# display.net
KiCad netlist of a schematic drawn in EAGLE
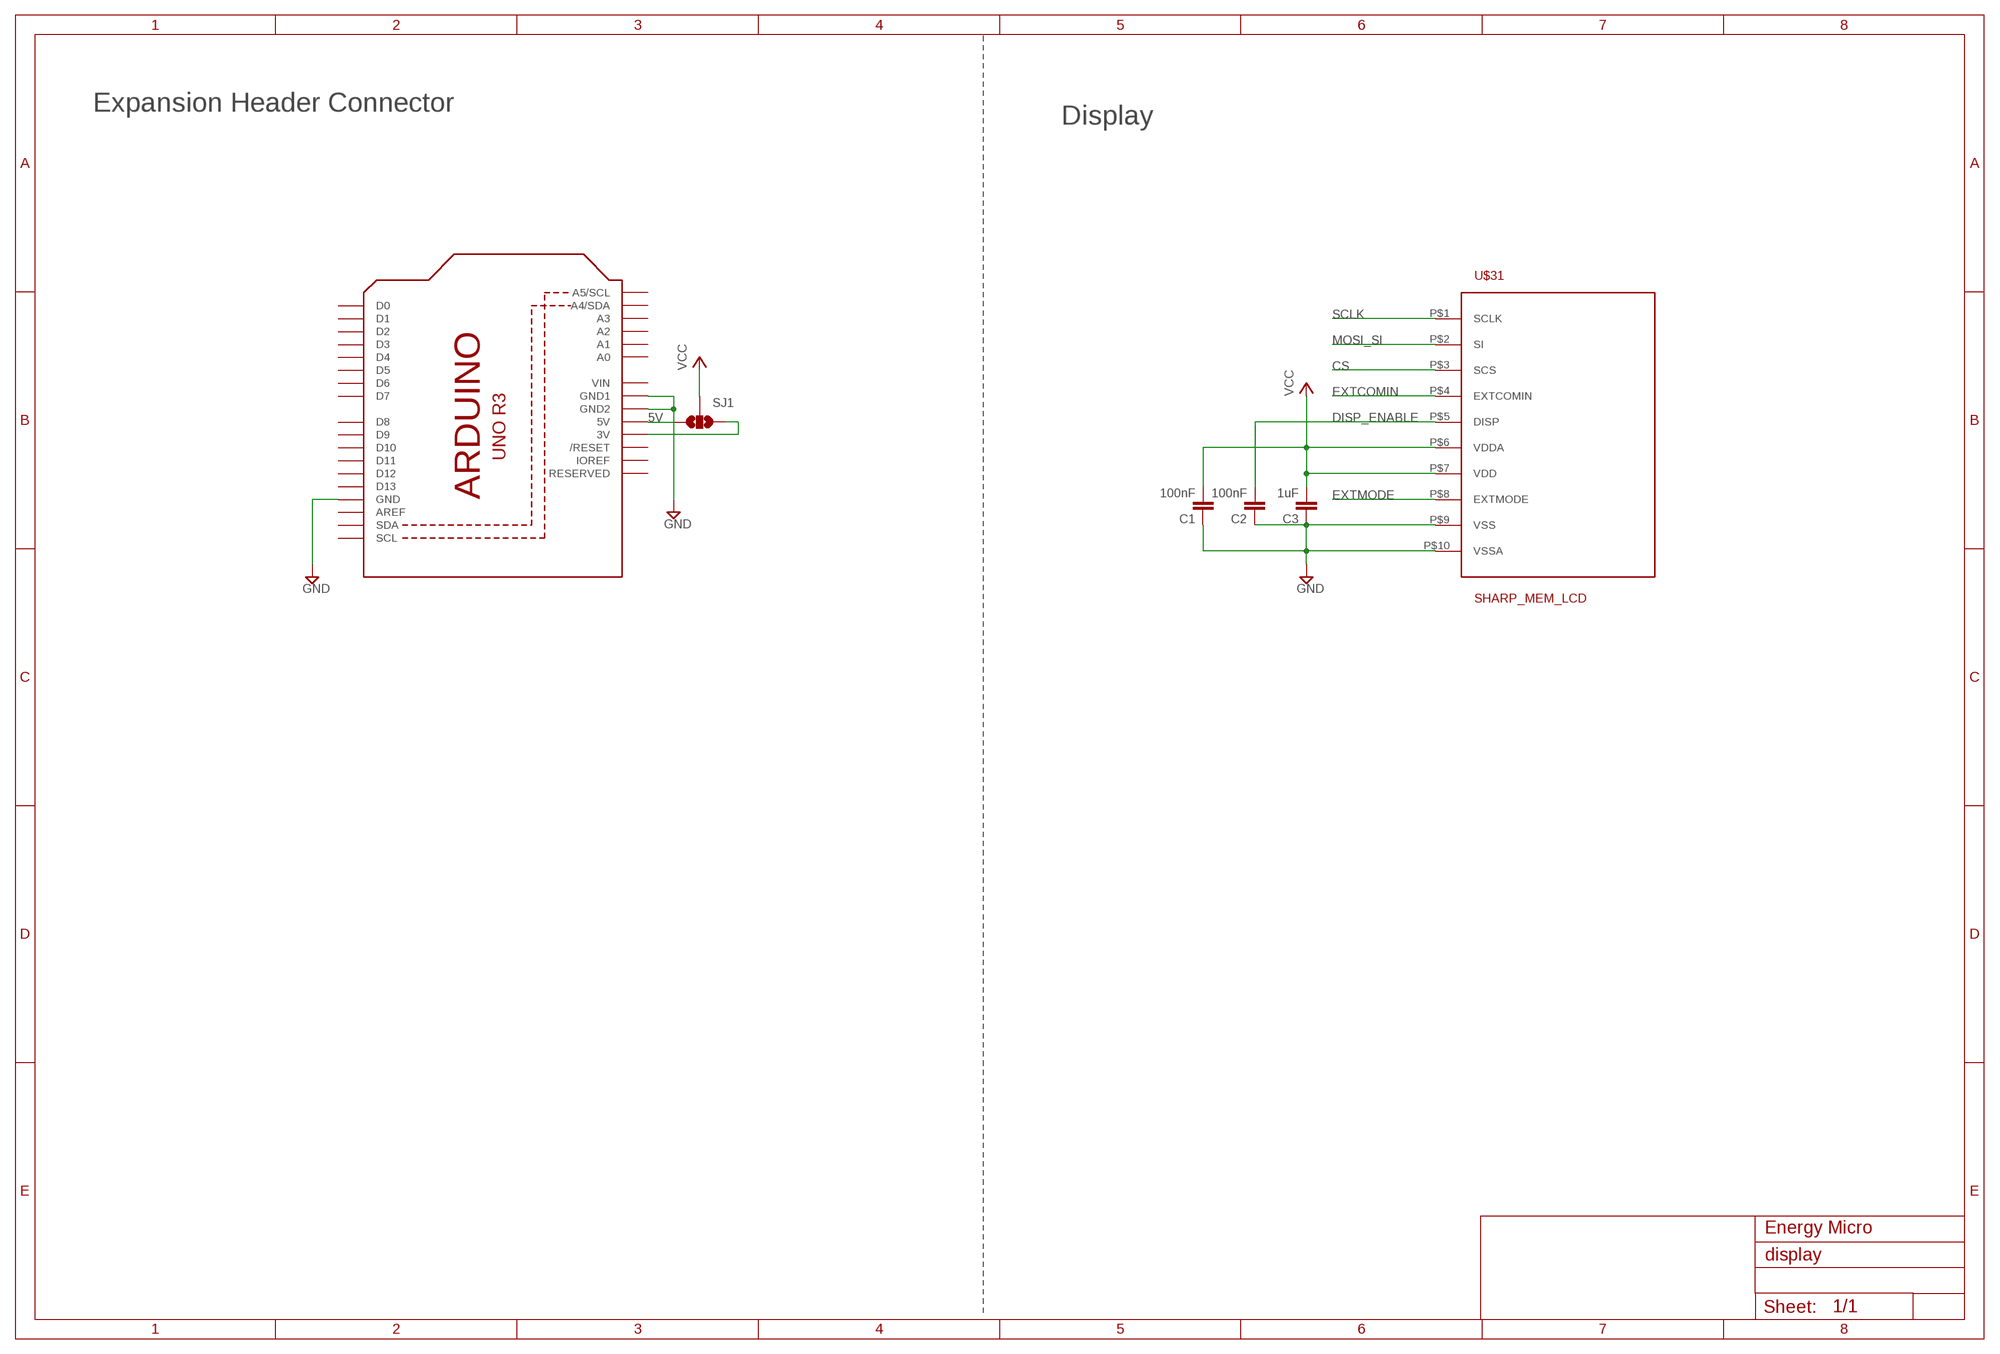
[diagram p0: schematic, sheet 1]

(export (version "E")
  (design (tool "Eeschema 10.0.6"))
  (components
    (comp (ref "C1")
      (value "100nF")
      (footprint "eagle-import:C0402K")
      (libsource (lib "eagle-import") (part "C-EUC0402K"))
    )
    (comp (ref "C2")
      (value "100nF")
      (footprint "eagle-import:C0402K")
      (libsource (lib "eagle-import") (part "C-EUC0402K"))
    )
    (comp (ref "C3")
      (value "1uF")
      (footprint "eagle-import:C0402K")
      (libsource (lib "eagle-import") (part "C-EUC0402K"))
    )
    (comp (ref "SJ1")
      (value "SOLDERJUMPER_2WAYT")
      (footprint "eagle-import:SJ_2")
      (libsource (lib "eagle-import") (part "SOLDERJUMPER_2WAYT"))
    )
    (comp (ref "U$31")
      (value "SHARP_MEM_LCD")
      (footprint "eagle-import:SHARP_MEM_LCD")
      (libsource (lib "eagle-import") (part "SHARP_MEM_LCD"))
    )
    (comp (ref "U1")
      (value "ARDUINOR3-MINI")
      (footprint "eagle-import:ARDUINOR3-MINI")
      (libsource (lib "eagle-import") (part "ARDUINOR3-MINI"))
    )
  )
  (nets
    (net (code "1") (name "/5V") (class "Default")
      (node (ref "SJ1") (pin "3") (pinfunction "3_3") (pintype "passive"))
      (node (ref "U1") (pin "5V") (pinfunction "5V_5V") (pintype "power_in"))
    )
    (net (code "2") (name "/CS") (class "Default")
      (node (ref "U$31") (pin "P$3") (pinfunction "SCS_P$3") (pintype "bidirectional"))
    )
    (net (code "3") (name "/DISP_ENABLE") (class "Default")
      (node (ref "C2") (pin "2") (pinfunction "2_2") (pintype "passive"))
      (node (ref "U$31") (pin "P$5") (pinfunction "DISP_P$5") (pintype "bidirectional"))
    )
    (net (code "4") (name "/EXTCOMIN") (class "Default")
      (node (ref "U$31") (pin "P$4") (pinfunction "EXTCOMIN_P$4") (pintype "bidirectional"))
    )
    (net (code "5") (name "/EXTMODE") (class "Default")
      (node (ref "U$31") (pin "P$8") (pinfunction "EXTMODE_P$8") (pintype "bidirectional"))
    )
    (net (code "6") (name "/MOSI_SI") (class "Default")
      (node (ref "U$31") (pin "P$2") (pinfunction "SI_P$2") (pintype "bidirectional"))
    )
    (net (code "7") (name "/SCLK") (class "Default")
      (node (ref "U$31") (pin "P$1") (pinfunction "SCLK_P$1") (pintype "bidirectional"))
    )
    (net (code "8") (name "/VIN") (class "Default")
      (node (ref "U1") (pin "VIN") (pinfunction "VIN_VIN") (pintype "power_in"))
    )
    (net (code "9") (name "GND") (class "Default")
      (node (ref "C1") (pin "1") (pinfunction "1_1") (pintype "passive"))
      (node (ref "C2") (pin "1") (pinfunction "1_1") (pintype "passive"))
      (node (ref "C3") (pin "1") (pinfunction "1_1") (pintype "passive"))
      (node (ref "U$31") (pin "P$10") (pinfunction "VSSA_P$10") (pintype "bidirectional"))
      (node (ref "U$31") (pin "P$9") (pinfunction "VSS_P$9") (pintype "bidirectional"))
      (node (ref "U1") (pin "GND") (pinfunction "GND_GND") (pintype "power_in"))
      (node (ref "U1") (pin "GND1") (pinfunction "GND1_GND1") (pintype "power_in"))
      (node (ref "U1") (pin "GND2") (pinfunction "GND2_GND2") (pintype "power_in"))
    )
    (net (code "10") (name "Net-(SJ1-Pad1)") (class "Default")
      (node (ref "SJ1") (pin "1") (pinfunction "1_1") (pintype "passive"))
      (node (ref "U1") (pin "3V") (pinfunction "3V_3V") (pintype "power_in"))
    )
    (net (code "11") (name "VCC") (class "Default")
      (node (ref "C1") (pin "2") (pinfunction "2_2") (pintype "passive"))
      (node (ref "C3") (pin "2") (pinfunction "2_2") (pintype "passive"))
      (node (ref "SJ1") (pin "2") (pinfunction "2_2") (pintype "passive"))
      (node (ref "U$31") (pin "P$6") (pinfunction "VDDA_P$6") (pintype "bidirectional"))
      (node (ref "U$31") (pin "P$7") (pinfunction "VDD_P$7") (pintype "bidirectional"))
    )
    (net (code "12") (name "unconnected-(U1-A4{slash}SDA-PadA4)") (class "Default")
      (node (ref "U1") (pin "A4") (pinfunction "A4/SDA_A4") (pintype "bidirectional"))
    )
    (net (code "13") (name "unconnected-(U1-A5{slash}SCL-PadA5)") (class "Default")
      (node (ref "U1") (pin "A5") (pinfunction "A5/SCL_A5") (pintype "bidirectional"))
    )
    (net (code "14") (name "unconnected-(U1-PadA0)") (class "Default")
      (node (ref "U1") (pin "A0") (pinfunction "A0_A0") (pintype "bidirectional"))
    )
    (net (code "15") (name "unconnected-(U1-PadA1)") (class "Default")
      (node (ref "U1") (pin "A1") (pinfunction "A1_A1") (pintype "bidirectional"))
    )
    (net (code "16") (name "unconnected-(U1-PadA2)") (class "Default")
      (node (ref "U1") (pin "A2") (pinfunction "A2_A2") (pintype "bidirectional"))
    )
    (net (code "17") (name "unconnected-(U1-PadA3)") (class "Default")
      (node (ref "U1") (pin "A3") (pinfunction "A3_A3") (pintype "bidirectional"))
    )
    (net (code "18") (name "unconnected-(U1-PadAREF)") (class "Default")
      (node (ref "U1") (pin "AREF") (pinfunction "AREF_AREF") (pintype "bidirectional"))
    )
    (net (code "19") (name "unconnected-(U1-PadD0)") (class "Default")
      (node (ref "U1") (pin "D0") (pinfunction "D0_D0") (pintype "bidirectional"))
    )
    (net (code "20") (name "unconnected-(U1-PadD1)") (class "Default")
      (node (ref "U1") (pin "D1") (pinfunction "D1_D1") (pintype "bidirectional"))
    )
    (net (code "21") (name "unconnected-(U1-PadD2)") (class "Default")
      (node (ref "U1") (pin "D2") (pinfunction "D2_D2") (pintype "bidirectional"))
    )
    (net (code "22") (name "unconnected-(U1-PadD3)") (class "Default")
      (node (ref "U1") (pin "D3") (pinfunction "D3_D3") (pintype "bidirectional"))
    )
    (net (code "23") (name "unconnected-(U1-PadD4)") (class "Default")
      (node (ref "U1") (pin "D4") (pinfunction "D4_D4") (pintype "bidirectional"))
    )
    (net (code "24") (name "unconnected-(U1-PadD5)") (class "Default")
      (node (ref "U1") (pin "D5") (pinfunction "D5_D5") (pintype "bidirectional"))
    )
    (net (code "25") (name "unconnected-(U1-PadD6)") (class "Default")
      (node (ref "U1") (pin "D6") (pinfunction "D6_D6") (pintype "bidirectional"))
    )
    (net (code "26") (name "unconnected-(U1-PadD7)") (class "Default")
      (node (ref "U1") (pin "D7") (pinfunction "D7_D7") (pintype "bidirectional"))
    )
    (net (code "27") (name "unconnected-(U1-PadD8)") (class "Default")
      (node (ref "U1") (pin "D8") (pinfunction "D8_D8") (pintype "bidirectional"))
    )
    (net (code "28") (name "unconnected-(U1-PadD9)") (class "Default")
      (node (ref "U1") (pin "D9") (pinfunction "D9_D9") (pintype "bidirectional"))
    )
    (net (code "29") (name "unconnected-(U1-PadD10)") (class "Default")
      (node (ref "U1") (pin "D10") (pinfunction "D10_D10") (pintype "bidirectional"))
    )
    (net (code "30") (name "unconnected-(U1-PadD11)") (class "Default")
      (node (ref "U1") (pin "D11") (pinfunction "D11_D11") (pintype "bidirectional"))
    )
    (net (code "31") (name "unconnected-(U1-PadD12)") (class "Default")
      (node (ref "U1") (pin "D12") (pinfunction "D12_D12") (pintype "bidirectional"))
    )
    (net (code "32") (name "unconnected-(U1-PadD13)") (class "Default")
      (node (ref "U1") (pin "D13") (pinfunction "D13_D13") (pintype "bidirectional"))
    )
    (net (code "33") (name "unconnected-(U1-PadIOREF)") (class "Default")
      (node (ref "U1") (pin "IOREF") (pinfunction "IOREF_IOREF") (pintype "output"))
    )
    (net (code "34") (name "unconnected-(U1-PadRESERVED)") (class "Default")
      (node (ref "U1") (pin "RESERVED") (pinfunction "RESERVED_RESERVED") (pintype "no_connect"))
    )
    (net (code "35") (name "unconnected-(U1-PadSCL)") (class "Default")
      (node (ref "U1") (pin "SCL") (pinfunction "SCL_SCL") (pintype "bidirectional"))
    )
    (net (code "36") (name "unconnected-(U1-PadSDA)") (class "Default")
      (node (ref "U1") (pin "SDA") (pinfunction "SDA_SDA") (pintype "bidirectional"))
    )
    (net (code "37") (name "unconnected-(U1-{slash}RESET-PadRESET)") (class "Default")
      (node (ref "U1") (pin "RESET") (pinfunction "/RESET_RESET") (pintype "bidirectional"))
    )
  )
)
